# AC_DC_CONTROL.net
KiCad netlist of a schematic drawn in Altium Designer
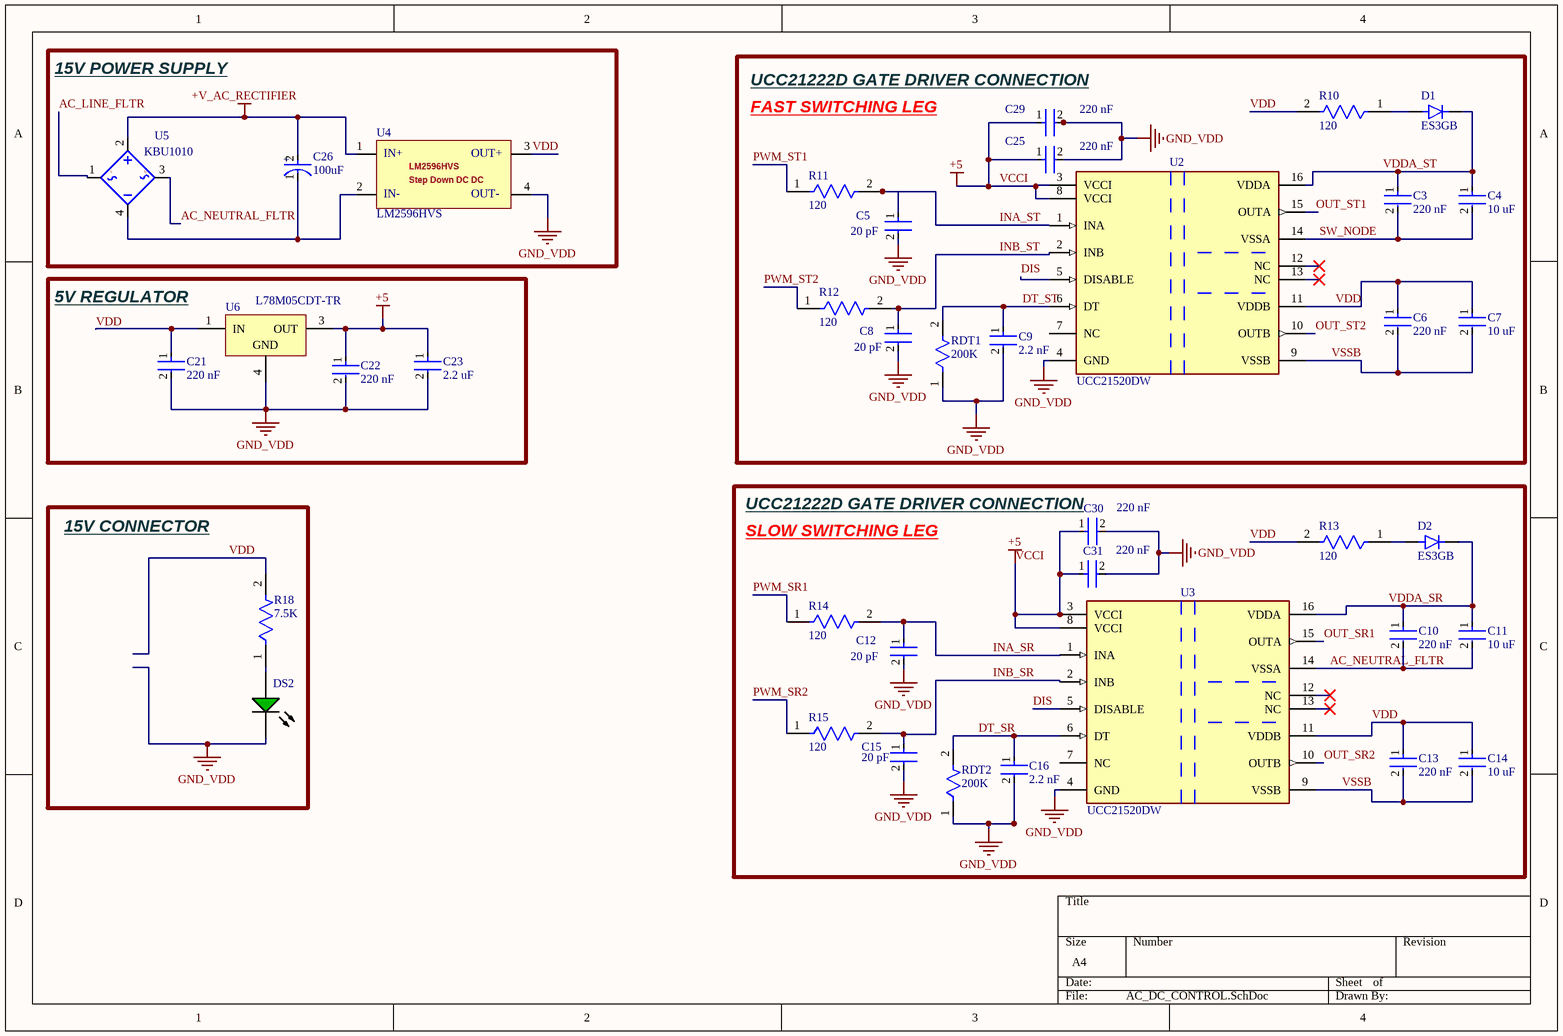
[diagram p0: AC_DC_CONTROL.SchDoc]

(export (version "E")
  (design (tool "Eeschema 10.0.6"))
  (components
    (comp (ref "C3")
      (value "220 nF")
      (footprint "FP-C0805C-DN-MFG")
      (description "CAP CER 0.22UF 50V X7R 0805")
      (fields
        (field (name "MANUFACTURER") "KEMET")
        (field (name "OCTOPART") "https://octopart.com/c0805c224k5ractu-kemet-144670")
      )
      (libsource (lib "Altium Content Vault") (part "b4654b650e69147ec39a6b967a45e02"))
    )
    (comp (ref "C4")
      (value "10 uF")
      (footprint "FP-C0805C-DN-MFG")
      (description "CAP CER 0.22UF 50V X7R 0805")
      (fields
        (field (name "MANUFACTURER") "KEMET")
        (field (name "OCTOPART") "https://octopart.com/c0805c224k5ractu-kemet-144670")
      )
      (libsource (lib "Altium Content Vault") (part "b4654b650e69147ec39a6b967a45e02"))
    )
    (comp (ref "C5")
      (value "20 pF")
      (footprint "FP-C0805C-DN-MFG")
      (description "CAP CER 0.22UF 50V X7R 0805")
      (fields
        (field (name "MANUFACTURER") "KEMET")
        (field (name "OCTOPART") "https://octopart.com/c0805c224k5ractu-kemet-144670")
      )
      (libsource (lib "Altium Content Vault") (part "b4654b650e69147ec39a6b967a45e02"))
    )
    (comp (ref "C6")
      (value "220 nF")
      (footprint "FP-C0805C-DN-MFG")
      (description "CAP CER 0.22UF 50V X7R 0805")
      (fields
        (field (name "MANUFACTURER") "KEMET")
        (field (name "OCTOPART") "https://octopart.com/c0805c224k5ractu-kemet-144670")
      )
      (libsource (lib "Altium Content Vault") (part "b4654b650e69147ec39a6b967a45e02"))
    )
    (comp (ref "C7")
      (value "10 uF")
      (footprint "FP-C0805C-DN-MFG")
      (description "CAP CER 0.22UF 50V X7R 0805")
      (fields
        (field (name "MANUFACTURER") "KEMET")
        (field (name "OCTOPART") "https://octopart.com/c0805c224k5ractu-kemet-144670")
      )
      (libsource (lib "Altium Content Vault") (part "b4654b650e69147ec39a6b967a45e02"))
    )
    (comp (ref "C8")
      (value "20 pF")
      (footprint "FP-C0805C-DN-MFG")
      (description "CAP CER 0.22UF 50V X7R 0805")
      (fields
        (field (name "MANUFACTURER") "KEMET")
        (field (name "OCTOPART") "https://octopart.com/c0805c224k5ractu-kemet-144670")
      )
      (libsource (lib "Altium Content Vault") (part "b4654b650e69147ec39a6b967a45e02"))
    )
    (comp (ref "C9")
      (value "2.2 nF")
      (footprint "FP-C0805C-DN-MFG")
      (description "CAP CER 0.22UF 50V X7R 0805")
      (fields
        (field (name "MANUFACTURER") "KEMET")
        (field (name "OCTOPART") "https://octopart.com/c0805c224k5ractu-kemet-144670")
      )
      (libsource (lib "Altium Content Vault") (part "b4654b650e69147ec39a6b967a45e02"))
    )
    (comp (ref "C10")
      (value "220 nF")
      (footprint "FP-C0805C-DN-MFG")
      (description "CAP CER 0.22UF 50V X7R 0805")
      (fields
        (field (name "MANUFACTURER") "KEMET")
        (field (name "OCTOPART") "https://octopart.com/c0805c224k5ractu-kemet-144670")
      )
      (libsource (lib "Altium Content Vault") (part "b4654b650e69147ec39a6b967a45e02"))
    )
    (comp (ref "C11")
      (value "10 uF")
      (footprint "FP-C0805C-DN-MFG")
      (description "CAP CER 0.22UF 50V X7R 0805")
      (fields
        (field (name "MANUFACTURER") "KEMET")
        (field (name "OCTOPART") "https://octopart.com/c0805c224k5ractu-kemet-144670")
      )
      (libsource (lib "Altium Content Vault") (part "b4654b650e69147ec39a6b967a45e02"))
    )
    (comp (ref "C12")
      (value "20 pF")
      (footprint "FP-C0805C-DN-MFG")
      (description "CAP CER 0.22UF 50V X7R 0805")
      (fields
        (field (name "MANUFACTURER") "KEMET")
        (field (name "OCTOPART") "https://octopart.com/c0805c224k5ractu-kemet-144670")
      )
      (libsource (lib "Altium Content Vault") (part "b4654b650e69147ec39a6b967a45e02"))
    )
    (comp (ref "C13")
      (value "220 nF")
      (footprint "FP-C0805C-DN-MFG")
      (description "CAP CER 0.22UF 50V X7R 0805")
      (fields
        (field (name "MANUFACTURER") "KEMET")
        (field (name "OCTOPART") "https://octopart.com/c0805c224k5ractu-kemet-144670")
      )
      (libsource (lib "Altium Content Vault") (part "b4654b650e69147ec39a6b967a45e02"))
    )
    (comp (ref "C14")
      (value "10 uF")
      (footprint "FP-C0805C-DN-MFG")
      (description "CAP CER 0.22UF 50V X7R 0805")
      (fields
        (field (name "MANUFACTURER") "KEMET")
        (field (name "OCTOPART") "https://octopart.com/c0805c224k5ractu-kemet-144670")
      )
      (libsource (lib "Altium Content Vault") (part "b4654b650e69147ec39a6b967a45e02"))
    )
    (comp (ref "C15")
      (value "20 pF")
      (footprint "FP-C0805C-DN-MFG")
      (description "CAP CER 0.22UF 50V X7R 0805")
      (fields
        (field (name "MANUFACTURER") "KEMET")
        (field (name "OCTOPART") "https://octopart.com/c0805c224k5ractu-kemet-144670")
      )
      (libsource (lib "Altium Content Vault") (part "b4654b650e69147ec39a6b967a45e02"))
    )
    (comp (ref "C16")
      (value "2.2 nF")
      (footprint "FP-C0805C-DN-MFG")
      (description "CAP CER 0.22UF 50V X7R 0805")
      (fields
        (field (name "MANUFACTURER") "KEMET")
        (field (name "OCTOPART") "https://octopart.com/c0805c224k5ractu-kemet-144670")
      )
      (libsource (lib "Altium Content Vault") (part "b4654b650e69147ec39a6b967a45e02"))
    )
    (comp (ref "C21")
      (value "220 nF")
      (footprint "FP-C0805C-DN-MFG")
      (description "CAP CER 0.22UF 50V X7R 0805")
      (fields
        (field (name "MANUFACTURER") "KEMET")
        (field (name "OCTOPART") "https://octopart.com/c0805c224k5ractu-kemet-144670")
      )
      (libsource (lib "Altium Content Vault") (part "b4654b650e69147ec39a6b967a45e02"))
    )
    (comp (ref "C22")
      (value "220 nF")
      (footprint "FP-C0805C-DN-MFG")
      (description "CAP CER 0.22UF 50V X7R 0805")
      (fields
        (field (name "MANUFACTURER") "KEMET")
        (field (name "OCTOPART") "https://octopart.com/c0805c224k5ractu-kemet-144670")
      )
      (libsource (lib "Altium Content Vault") (part "b4654b650e69147ec39a6b967a45e02"))
    )
    (comp (ref "C23")
      (value "2.2 uF")
      (footprint "FP-C0805C-DN-MFG")
      (description "CAP CER 0.22UF 50V X7R 0805")
      (fields
        (field (name "MANUFACTURER") "KEMET")
        (field (name "OCTOPART") "https://octopart.com/c0805c224k5ractu-kemet-144670")
      )
      (libsource (lib "Altium Content Vault") (part "b4654b650e69147ec39a6b967a45e02"))
    )
    (comp (ref "C25")
      (value "220 nF")
      (footprint "FP-C0805C-DN-MFG")
      (description "CAP CER 0.22UF 50V X7R 0805")
      (fields
        (field (name "MANUFACTURER") "KEMET")
        (field (name "OCTOPART") "https://octopart.com/c0805c224k5ractu-kemet-144670")
      )
      (libsource (lib "Altium Content Vault") (part "b4654b650e69147ec39a6b967a45e02"))
    )
    (comp (ref "C26")
      (value "100uF")
      (footprint "FP-RAD-TH-D_10_0_5-L_30_2-MFG")
      (description "Aluminum Electrolytic Capacitors (Radial Lead Type) AEC-Q200 Qualified 100uF ±20% 100V")
      (fields (field (name "TOLERANCE") "20%") (field (name "VOLTAGE") "100V"))
      (libsource (lib "Altium Content Vault") (part "a00bbbee19879c290e62620ae7e47b1"))
    )
    (comp (ref "C29")
      (value "220 nF")
      (footprint "FP-C0805C-DN-MFG")
      (description "CAP CER 0.22UF 50V X7R 0805")
      (fields
        (field (name "MANUFACTURER") "KEMET")
        (field (name "OCTOPART") "https://octopart.com/c0805c224k5ractu-kemet-144670")
      )
      (libsource (lib "Altium Content Vault") (part "b4654b650e69147ec39a6b967a45e02"))
    )
    (comp (ref "C30")
      (value "220 nF")
      (footprint "FP-C0805C-DN-MFG")
      (description "CAP CER 0.22UF 50V X7R 0805")
      (fields
        (field (name "MANUFACTURER") "KEMET")
        (field (name "OCTOPART") "https://octopart.com/c0805c224k5ractu-kemet-144670")
      )
      (libsource (lib "Altium Content Vault") (part "b4654b650e69147ec39a6b967a45e02"))
    )
    (comp (ref "C31")
      (value "220 nF")
      (footprint "FP-C0805C-DN-MFG")
      (description "CAP CER 0.22UF 50V X7R 0805")
      (fields
        (field (name "MANUFACTURER") "KEMET")
        (field (name "OCTOPART") "https://octopart.com/c0805c224k5ractu-kemet-144670")
      )
      (libsource (lib "Altium Content Vault") (part "b4654b650e69147ec39a6b967a45e02"))
    )
    (comp (ref "D1")
      (value "ES3GB")
      (footprint "ES3GB:DIOM4336X265N")
      (fields (field (name "MF") "{'manufacturer': u'Taiwan Semiconductor'}"))
      (libsource (lib "*") (part "ES3GB"))
    )
    (comp (ref "D2")
      (value "ES3GB")
      (footprint "ES3GB:DIOM4336X265N")
      (fields (field (name "MF") "{'manufacturer': u'Taiwan Semiconductor'}"))
      (libsource (lib "*") (part "ES3GB"))
    )
    (comp (ref "DS2")
      (value "HSMG-C170")
      (footprint "AVAG-HSMX-C170_V")
      (description "Chip LED, Green, 2.2 V, -40 to 85 degC, 2-Pin SMD, Pb-Free, Tape and Reel")
      (fields (field (name "MANUFACTURER") "Avago"))
      (libsource (lib "Altium Content Vault") (part "LED_GREEN_A1K2-2"))
    )
    (comp (ref "R10")
      (value "120")
      (footprint "FP-RC0805-0_6-IPC_C")
      (description "RES 100K OHM 1% 1/8W 0805")
      (fields (field (name "TOLERANCE") "1%"))
      (libsource (lib "Altium Content Vault") (part "1029c3af85768c4190bb7ad29bc67b5"))
    )
    (comp (ref "R11")
      (value "120")
      (footprint "FP-RC0805-0_6-IPC_C")
      (description "RES 100K OHM 1% 1/8W 0805")
      (fields (field (name "TOLERANCE") "1%"))
      (libsource (lib "Altium Content Vault") (part "1029c3af85768c4190bb7ad29bc67b5"))
    )
    (comp (ref "R12")
      (value "120")
      (footprint "FP-RC0805-0_6-IPC_C")
      (description "RES 100K OHM 1% 1/8W 0805")
      (fields (field (name "TOLERANCE") "1%"))
      (libsource (lib "Altium Content Vault") (part "1029c3af85768c4190bb7ad29bc67b5"))
    )
    (comp (ref "R13")
      (value "120")
      (footprint "FP-RC0805-0_6-IPC_C")
      (description "RES 100K OHM 1% 1/8W 0805")
      (fields (field (name "TOLERANCE") "1%"))
      (libsource (lib "Altium Content Vault") (part "1029c3af85768c4190bb7ad29bc67b5"))
    )
    (comp (ref "R14")
      (value "120")
      (footprint "FP-RC0805-0_6-IPC_C")
      (description "RES 100K OHM 1% 1/8W 0805")
      (fields (field (name "TOLERANCE") "1%"))
      (libsource (lib "Altium Content Vault") (part "1029c3af85768c4190bb7ad29bc67b5"))
    )
    (comp (ref "R15")
      (value "120")
      (footprint "FP-RC0805-0_6-IPC_C")
      (description "RES 100K OHM 1% 1/8W 0805")
      (fields (field (name "TOLERANCE") "1%"))
      (libsource (lib "Altium Content Vault") (part "1029c3af85768c4190bb7ad29bc67b5"))
    )
    (comp (ref "R18")
      (value "7.5K")
      (footprint "FP-RC0805-0_6-IPC_C")
      (description "RES 100K OHM 1% 1/8W 0805")
      (fields (field (name "TOLERANCE") "1%"))
      (libsource (lib "Altium Content Vault") (part "1029c3af85768c4190bb7ad29bc67b5"))
    )
    (comp (ref "RDT1")
      (value "200K")
      (footprint "PCBComponent_1")
      (libsource (lib "RES_0.125W_AXIAL") (part "RES"))
    )
    (comp (ref "RDT2")
      (value "200K")
      (footprint "PCBComponent_1")
      (libsource (lib "RES_0.125W_AXIAL") (part "RES"))
    )
    (comp (ref "U2")
      (value "UCC21520DW")
      (footprint "FP-DW0016B-MFG")
      (description "DGTL ISO 5.7KV GATE DRVR 16SOIC")
      (libsource (lib "Altium Content Vault") (part "6a37a0897a27c2327358918c0ee180b"))
    )
    (comp (ref "U3")
      (value "UCC21520DW")
      (footprint "FP-DW0016B-MFG")
      (description "DGTL ISO 5.7KV GATE DRVR 16SOIC")
      (libsource (lib "Altium Content Vault") (part "6a37a0897a27c2327358918c0ee180b"))
    )
    (comp (ref "U4")
      (value "LM2596HVS")
      (footprint "PCBComponent_1")
      (libsource (lib "LM2596HVS") (part "LM2596HVS"))
    )
    (comp (ref "U5")
      (value "KBU1010")
      (footprint "PCBComponent_1")
      (libsource (lib "KBU1010") (part "KBU1010"))
    )
    (comp (ref "U6")
      (value "L78M05CDT-TR")
      (footprint "TO-252_L")
      (description "Positive Voltage Regulator, 5V, 3-Pin DPAK, Tape and Reel")
      (libsource (lib "Altium Content Vault") (part "PM-REG-L4940-SOT3"))
    )
  )
  (nets
    (net (code "1") (name "+5") (class "Default")
      (node (ref "C22") (pin "1") (pinfunction "1_1") (pintype "passive"))
      (node (ref "C23") (pin "1") (pinfunction "1_1") (pintype "passive"))
      (node (ref "C25") (pin "1") (pinfunction "1_1") (pintype "passive"))
      (node (ref "C29") (pin "1") (pinfunction "1_1") (pintype "passive"))
      (node (ref "C30") (pin "1") (pinfunction "1_1") (pintype "passive"))
      (node (ref "C31") (pin "1") (pinfunction "1_1") (pintype "passive"))
      (node (ref "U2") (pin "3") (pinfunction "VCCI_3") (pintype "power_in"))
      (node (ref "U2") (pin "8") (pinfunction "VCCI_8") (pintype "power_in"))
      (node (ref "U3") (pin "3") (pinfunction "VCCI_3") (pintype "power_in"))
      (node (ref "U3") (pin "8") (pinfunction "VCCI_8") (pintype "power_in"))
      (node (ref "U6") (pin "3") (pinfunction "OUT_3") (pintype "power_in"))
    )
    (net (code "2") (name "+V_AC_RECTIFIER") (class "Default")
      (node (ref "C26") (pin "2") (pinfunction "A_2") (pintype "passive"))
      (node (ref "U4") (pin "1") (pinfunction "1_1") (pintype "passive"))
      (node (ref "U5") (pin "2") (pinfunction "2_2") (pintype "passive"))
    )
    (net (code "3") (name "/AC_LINE_FLTR") (class "Default")
      (node (ref "U5") (pin "1") (pinfunction "1_1") (pintype "passive"))
    )
    (net (code "4") (name "/AC_NEUTRAL_FLTR") (class "Default")
      (node (ref "C10") (pin "2") (pinfunction "2_2") (pintype "passive"))
      (node (ref "C11") (pin "2") (pinfunction "2_2") (pintype "passive"))
      (node (ref "U3") (pin "14") (pinfunction "VSSA_14") (pintype "power_in"))
      (node (ref "U5") (pin "3") (pinfunction "3_3") (pintype "passive"))
    )
    (net (code "5") (name "/DIS") (class "Default")
      (node (ref "U2") (pin "5") (pinfunction "DISABLE_5") (pintype "input"))
      (node (ref "U3") (pin "5") (pinfunction "DISABLE_5") (pintype "input"))
    )
    (net (code "6") (name "/DT_SR") (class "Default")
      (node (ref "C16") (pin "1") (pinfunction "1_1") (pintype "passive"))
      (node (ref "RDT2") (pin "2") (pinfunction "2_2") (pintype "passive"))
      (node (ref "U3") (pin "6") (pinfunction "DT_6") (pintype "input"))
    )
    (net (code "7") (name "/DT_ST") (class "Default")
      (node (ref "C9") (pin "1") (pinfunction "1_1") (pintype "passive"))
      (node (ref "RDT1") (pin "2") (pinfunction "2_2") (pintype "passive"))
      (node (ref "U2") (pin "6") (pinfunction "DT_6") (pintype "input"))
    )
    (net (code "8") (name "/INA_SR") (class "Default")
      (node (ref "C12") (pin "1") (pinfunction "1_1") (pintype "passive"))
      (node (ref "R14") (pin "2") (pinfunction "2_2") (pintype "passive"))
      (node (ref "U3") (pin "1") (pinfunction "INA_1") (pintype "input"))
    )
    (net (code "9") (name "/INA_ST") (class "Default")
      (node (ref "C5") (pin "1") (pinfunction "1_1") (pintype "passive"))
      (node (ref "R11") (pin "2") (pinfunction "2_2") (pintype "passive"))
      (node (ref "U2") (pin "1") (pinfunction "INA_1") (pintype "input"))
    )
    (net (code "10") (name "/INB_SR") (class "Default")
      (node (ref "C15") (pin "1") (pinfunction "1_1") (pintype "passive"))
      (node (ref "R15") (pin "2") (pinfunction "2_2") (pintype "passive"))
      (node (ref "U3") (pin "2") (pinfunction "INB_2") (pintype "input"))
    )
    (net (code "11") (name "/INB_ST") (class "Default")
      (node (ref "C8") (pin "1") (pinfunction "1_1") (pintype "passive"))
      (node (ref "R12") (pin "2") (pinfunction "2_2") (pintype "passive"))
      (node (ref "U2") (pin "2") (pinfunction "INB_2") (pintype "input"))
    )
    (net (code "12") (name "/OUT_SR1") (class "Default")
      (node (ref "U3") (pin "15") (pinfunction "OUTA_15") (pintype "output"))
    )
    (net (code "13") (name "/OUT_SR2") (class "Default")
      (node (ref "U3") (pin "10") (pinfunction "OUTB_10") (pintype "output"))
    )
    (net (code "14") (name "/OUT_ST1") (class "Default")
      (node (ref "U2") (pin "15") (pinfunction "OUTA_15") (pintype "output"))
    )
    (net (code "15") (name "/OUT_ST2") (class "Default")
      (node (ref "U2") (pin "10") (pinfunction "OUTB_10") (pintype "output"))
    )
    (net (code "16") (name "/PWM_SR1") (class "Default")
      (node (ref "R14") (pin "1") (pinfunction "1_1") (pintype "passive"))
    )
    (net (code "17") (name "/PWM_SR2") (class "Default")
      (node (ref "R15") (pin "1") (pinfunction "1_1") (pintype "passive"))
    )
    (net (code "18") (name "/PWM_ST1") (class "Default")
      (node (ref "R11") (pin "1") (pinfunction "1_1") (pintype "passive"))
    )
    (net (code "19") (name "/PWM_ST2") (class "Default")
      (node (ref "R12") (pin "1") (pinfunction "1_1") (pintype "passive"))
    )
    (net (code "20") (name "/SW_NODE") (class "Default")
      (node (ref "C3") (pin "2") (pinfunction "2_2") (pintype "passive"))
      (node (ref "C4") (pin "2") (pinfunction "2_2") (pintype "passive"))
      (node (ref "U2") (pin "14") (pinfunction "VSSA_14") (pintype "power_in"))
    )
    (net (code "21") (name "/VDD") (class "Default")
      (node (ref "C13") (pin "1") (pinfunction "1_1") (pintype "passive"))
      (node (ref "C14") (pin "1") (pinfunction "1_1") (pintype "passive"))
      (node (ref "C21") (pin "1") (pinfunction "1_1") (pintype "passive"))
      (node (ref "C6") (pin "1") (pinfunction "1_1") (pintype "passive"))
      (node (ref "C7") (pin "1") (pinfunction "1_1") (pintype "passive"))
      (node (ref "R10") (pin "2") (pinfunction "2_2") (pintype "passive"))
      (node (ref "R13") (pin "2") (pinfunction "2_2") (pintype "passive"))
      (node (ref "R18") (pin "2") (pinfunction "2_2") (pintype "passive"))
      (node (ref "U2") (pin "11") (pinfunction "VDDB_11") (pintype "power_in"))
      (node (ref "U3") (pin "11") (pinfunction "VDDB_11") (pintype "power_in"))
      (node (ref "U4") (pin "3") (pinfunction "3_3") (pintype "passive"))
      (node (ref "U6") (pin "1") (pinfunction "IN_1") (pintype "power_in"))
    )
    (net (code "22") (name "/VDDA_SR") (class "Default")
      (node (ref "C10") (pin "1") (pinfunction "1_1") (pintype "passive"))
      (node (ref "C11") (pin "1") (pinfunction "1_1") (pintype "passive"))
      (node (ref "D2") (pin "C") (pinfunction "K_C") (pintype "passive"))
      (node (ref "U3") (pin "16") (pinfunction "VDDA_16") (pintype "power_in"))
    )
    (net (code "23") (name "/VDDA_ST") (class "Default")
      (node (ref "C3") (pin "1") (pinfunction "1_1") (pintype "passive"))
      (node (ref "C4") (pin "1") (pinfunction "1_1") (pintype "passive"))
      (node (ref "D1") (pin "C") (pinfunction "K_C") (pintype "passive"))
      (node (ref "U2") (pin "16") (pinfunction "VDDA_16") (pintype "power_in"))
    )
    (net (code "24") (name "/VSSB") (class "Default")
      (node (ref "C13") (pin "2") (pinfunction "2_2") (pintype "passive"))
      (node (ref "C14") (pin "2") (pinfunction "2_2") (pintype "passive"))
      (node (ref "C6") (pin "2") (pinfunction "2_2") (pintype "passive"))
      (node (ref "C7") (pin "2") (pinfunction "2_2") (pintype "passive"))
      (node (ref "U2") (pin "9") (pinfunction "VSSB_9") (pintype "power_in"))
      (node (ref "U3") (pin "9") (pinfunction "VSSB_9") (pintype "power_in"))
    )
    (net (code "25") (name "GND_VDD") (class "Default")
      (node (ref "C12") (pin "2") (pinfunction "2_2") (pintype "passive"))
      (node (ref "C15") (pin "2") (pinfunction "2_2") (pintype "passive"))
      (node (ref "C16") (pin "2") (pinfunction "2_2") (pintype "passive"))
      (node (ref "C21") (pin "2") (pinfunction "2_2") (pintype "passive"))
      (node (ref "C22") (pin "2") (pinfunction "2_2") (pintype "passive"))
      (node (ref "C23") (pin "2") (pinfunction "2_2") (pintype "passive"))
      (node (ref "C25") (pin "2") (pinfunction "2_2") (pintype "passive"))
      (node (ref "C29") (pin "2") (pinfunction "2_2") (pintype "passive"))
      (node (ref "C30") (pin "2") (pinfunction "2_2") (pintype "passive"))
      (node (ref "C31") (pin "2") (pinfunction "2_2") (pintype "passive"))
      (node (ref "C5") (pin "2") (pinfunction "2_2") (pintype "passive"))
      (node (ref "C8") (pin "2") (pinfunction "2_2") (pintype "passive"))
      (node (ref "C9") (pin "2") (pinfunction "2_2") (pintype "passive"))
      (node (ref "DS2") (pin "2") (pinfunction "K_2") (pintype "passive"))
      (node (ref "RDT1") (pin "1") (pinfunction "1_1") (pintype "passive"))
      (node (ref "RDT2") (pin "1") (pinfunction "1_1") (pintype "passive"))
      (node (ref "U2") (pin "4") (pinfunction "GND_4") (pintype "power_in"))
      (node (ref "U3") (pin "4") (pinfunction "GND_4") (pintype "power_in"))
      (node (ref "U4") (pin "4") (pinfunction "4_4") (pintype "passive"))
      (node (ref "U6") (pin "4") (pinfunction "GND_4") (pintype "power_in"))
    )
    (net (code "26") (name "Net-(C26-C)") (class "Default")
      (node (ref "C26") (pin "1") (pinfunction "C_1") (pintype "passive"))
      (node (ref "U4") (pin "2") (pinfunction "2_2") (pintype "passive"))
      (node (ref "U5") (pin "4") (pinfunction "4_4") (pintype "passive"))
    )
    (net (code "27") (name "Net-(D1-PadA)") (class "Default")
      (node (ref "D1") (pin "A") (pinfunction "A_A") (pintype "passive"))
      (node (ref "R10") (pin "1") (pinfunction "1_1") (pintype "passive"))
    )
    (net (code "28") (name "Net-(D2-PadA)") (class "Default")
      (node (ref "D2") (pin "A") (pinfunction "A_A") (pintype "passive"))
      (node (ref "R13") (pin "1") (pinfunction "1_1") (pintype "passive"))
    )
    (net (code "29") (name "Net-(DS2-A)") (class "Default")
      (node (ref "DS2") (pin "1") (pinfunction "A_1") (pintype "passive"))
      (node (ref "R18") (pin "1") (pinfunction "1_1") (pintype "passive"))
    )
    (net (code "30") (name "unconnected-(U2-NC-Pad7)") (class "Default")
      (node (ref "U2") (pin "7") (pinfunction "NC_7") (pintype "passive"))
    )
    (net (code "31") (name "unconnected-(U2-NC-Pad12)") (class "Default")
      (node (ref "U2") (pin "12") (pinfunction "NC_12") (pintype "passive+no_connect"))
    )
    (net (code "32") (name "unconnected-(U2-NC-Pad13)") (class "Default")
      (node (ref "U2") (pin "13") (pinfunction "NC_13") (pintype "passive+no_connect"))
    )
    (net (code "33") (name "unconnected-(U3-NC-Pad7)") (class "Default")
      (node (ref "U3") (pin "7") (pinfunction "NC_7") (pintype "passive"))
    )
    (net (code "34") (name "unconnected-(U3-NC-Pad12)") (class "Default")
      (node (ref "U3") (pin "12") (pinfunction "NC_12") (pintype "passive+no_connect"))
    )
    (net (code "35") (name "unconnected-(U3-NC-Pad13)") (class "Default")
      (node (ref "U3") (pin "13") (pinfunction "NC_13") (pintype "passive+no_connect"))
    )
  )
)
